# 18-OSPI_FLASH_AND_SPI_NOR_FLASH.net
KiCad netlist of a schematic drawn in Altium Designer
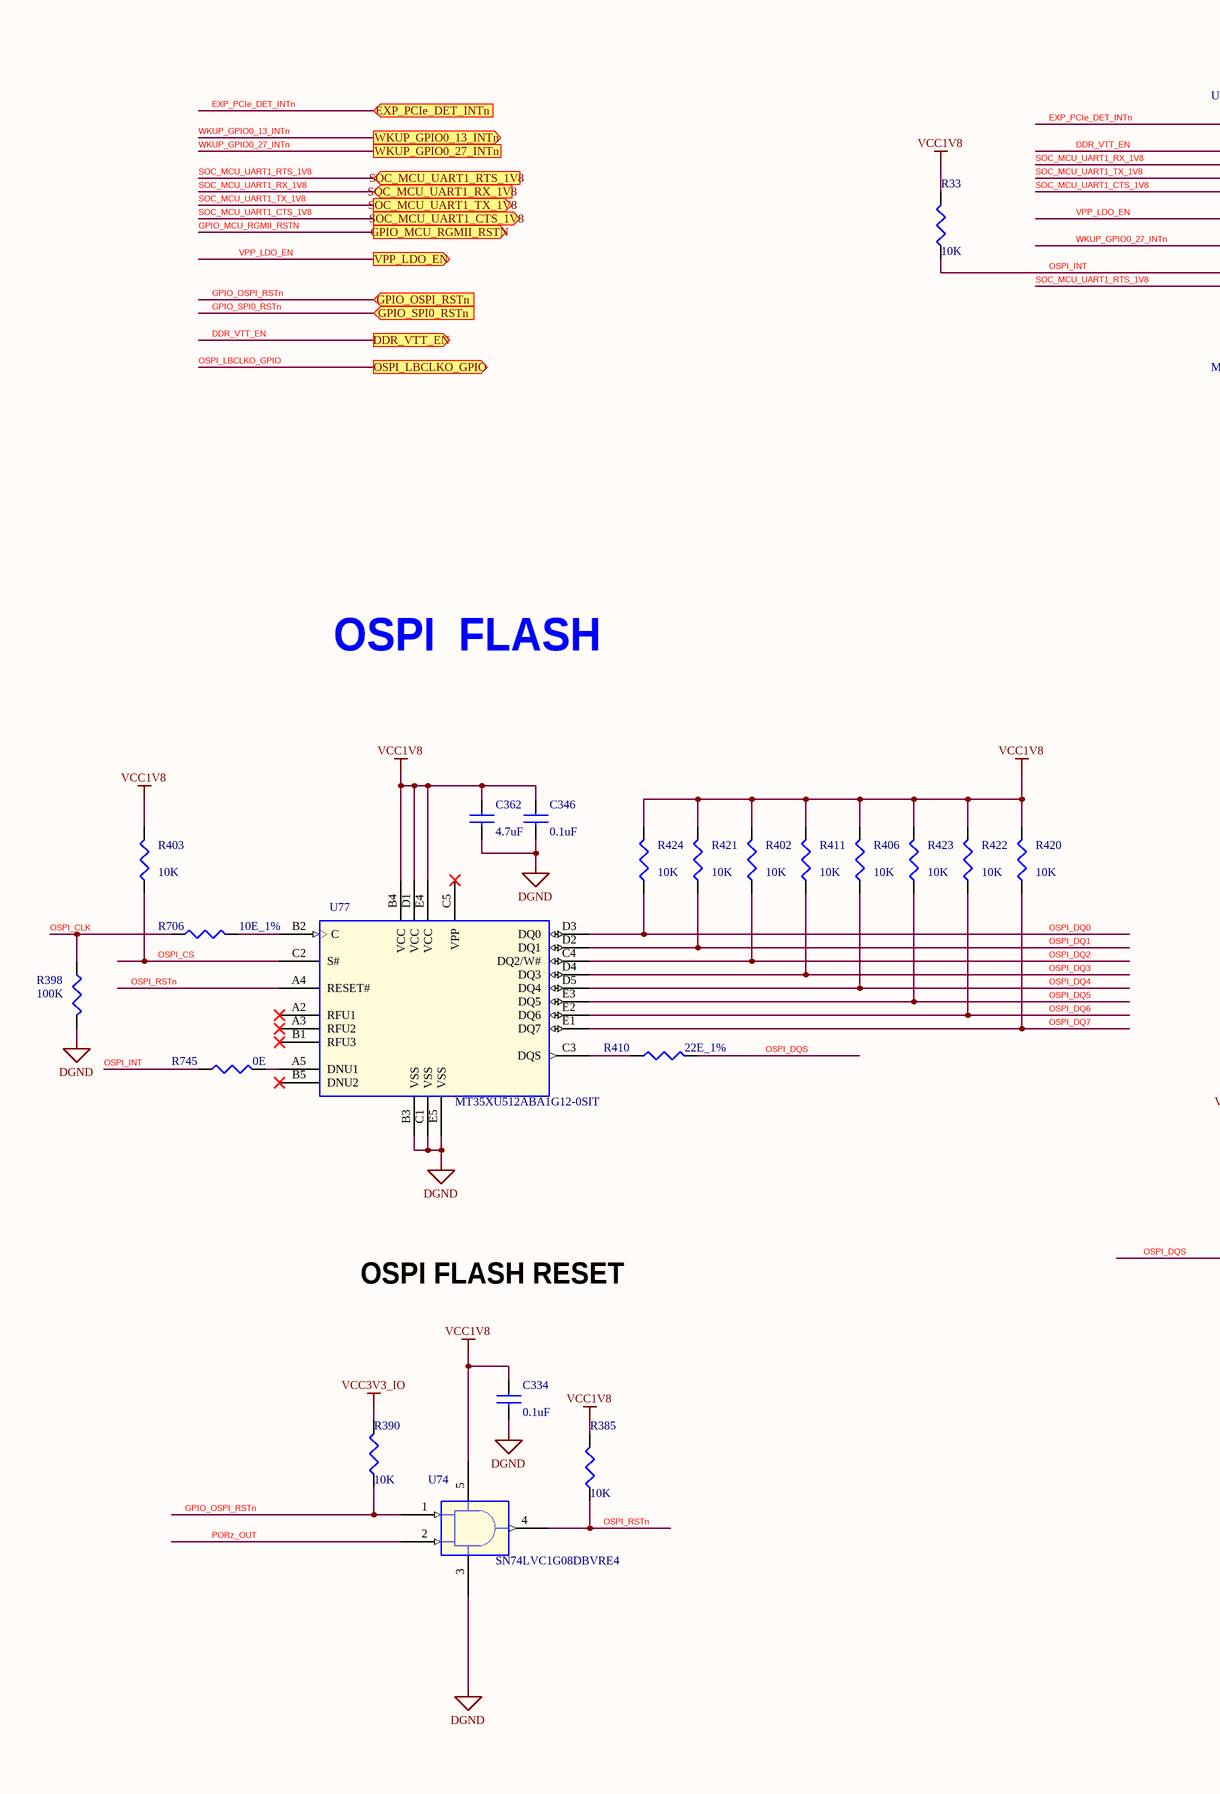
[diagram p0: 18-OSPI FLASH AND SPI NOR FLASH.SchDoc, left]
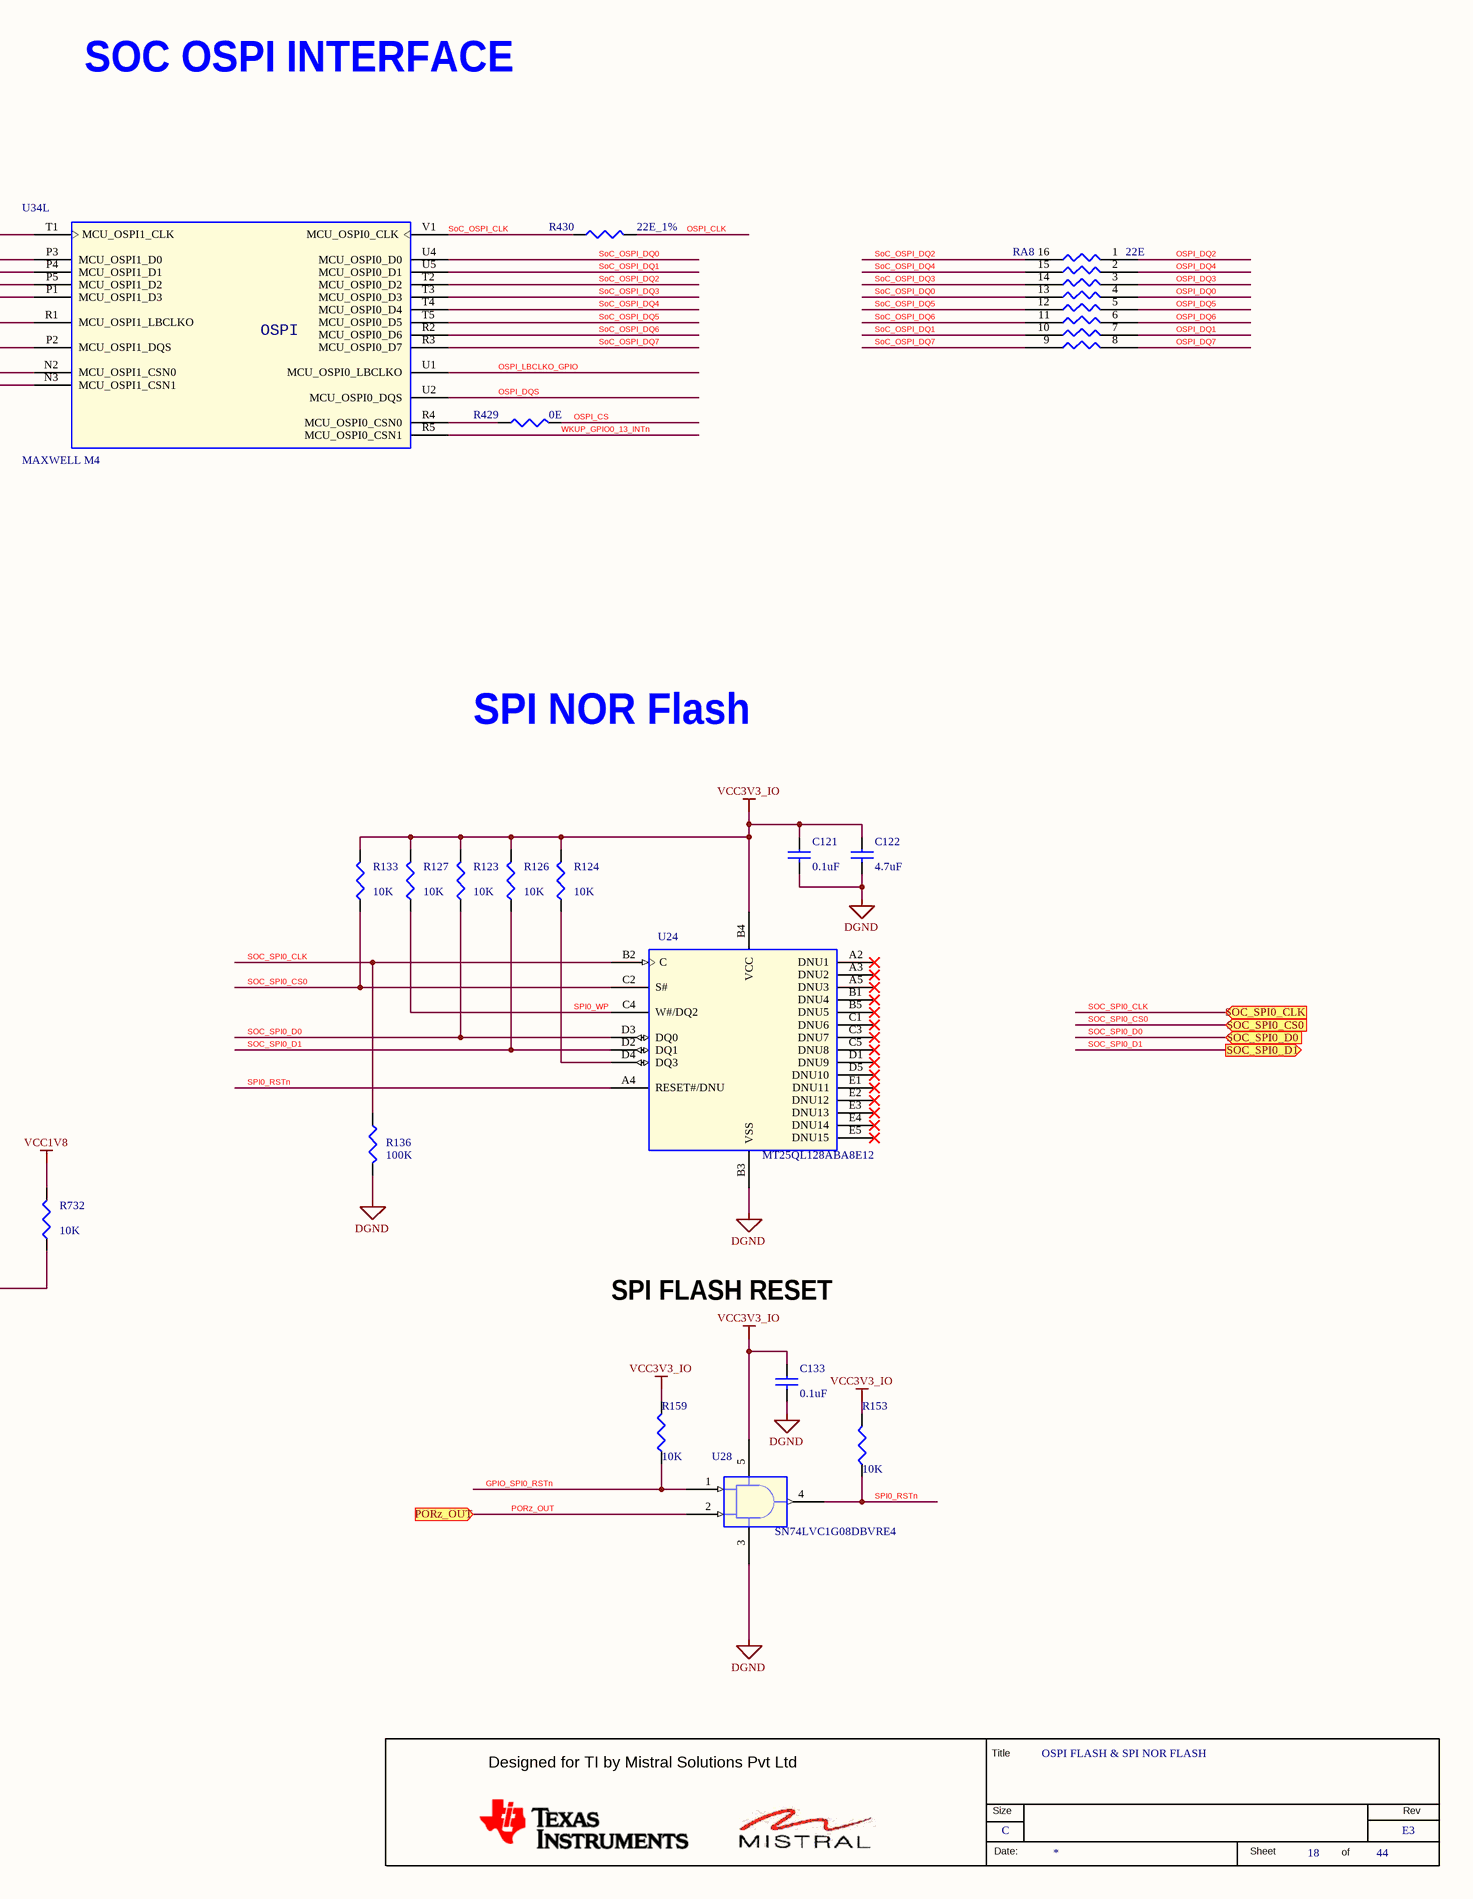
[diagram p1: 18-OSPI FLASH AND SPI NOR FLASH.SchDoc, right]

(export (version "E")
  (design (tool "Eeschema 10.0.6"))
  (components
    (comp (ref "C121")
      (value "0.1uF")
      (footprint "CAP0201_0-5")
      (description "CAP CERAMIC 0.1uF 16V 10% X5R 0201")
      (fields (field (name "DISTRIBUTOR_PART_NUMBER") "490-16742-1-ND") (field (name "VOLTAGE") "16V"))
      (libsource (lib "*") (part "CAP_Dup5"))
    )
    (comp (ref "C122")
      (value "4.7uF")
      (footprint "CAP0402_0-75")
      (description "CAP CERAMIC 4.7uF 10V 20% X5R 0402")
      (fields
        (field (name "MISTRAL PART NO") "120012060002-R")
        (field (name "MFR_PART_NUMBER") "0402ZD475MAT2A")
      )
      (libsource (lib "*") (part "CAP_Dup5"))
    )
    (comp (ref "C133")
      (value "0.1uF")
      (footprint "CAP0201_0-5")
      (description "CAP CERAMIC 0.1uF 16V 10% X5R 0201")
      (fields
        (field (name "MISTRAL PART NO") "120009030072-R")
        (field (name "MFR_PART_NUMBER") "GRM033R61C104KE84J")
      )
      (libsource (lib "*") (part "CAP_Dup5"))
    )
    (comp (ref "C334")
      (value "0.1uF")
      (footprint "CAP0201_0-5")
      (description "CAP CERAMIC 0.1uF 16V 10% X5R 0201")
      (fields (field (name "DISTRIBUTOR_PART_NUMBER") "490-16742-1-ND") (field (name "VOLTAGE") "16V"))
      (libsource (lib "*") (part "CAP_Dup5"))
    )
    (comp (ref "C346")
      (value "0.1uF")
      (footprint "CAP0201_0-5")
      (description "CAP CERAMIC 0.1uF 16V 10% X5R 0201")
      (fields (field (name "DISTRIBUTOR_PART_NUMBER") "490-16742-1-ND") (field (name "VOLTAGE") "16V"))
      (libsource (lib "*") (part "CAP_Dup5"))
    )
    (comp (ref "C362")
      (value "4.7uF")
      (footprint "CAP0402_0-75")
      (description "CAP CERAMIC 4.7uF 10V 20% X5R 0402")
      (fields (field (name "DISTRIBUTOR_PART_NUMBER") "478-10791-1-ND") (field (name "VOLTAGE") "10V"))
      (libsource (lib "*") (part "CAP_Dup5"))
    )
    (comp (ref "R33")
      (value "10K")
      (footprint "RES0402_0-5")
      (description "RES 10K 1/16W 5% 0402")
      (fields (field (name "DISTRIBUTOR_PART_NUMBER") "311-10KJRCT-ND") (field (name "VOLTAGE") "NA"))
      (libsource (lib "*") (part "RESISTOR_Dup5"))
    )
    (comp (ref "R123")
      (value "10K")
      (footprint "RES0402_0-5")
      (description "RES 10K 1/16W 5% 0402")
      (fields
        (field (name "MISTRAL PART NO") "110009030208-R")
        (field (name "MFR_PART_NUMBER") "RC0402JR-0710KL")
      )
      (libsource (lib "*") (part "RESISTOR_Dup5"))
    )
    (comp (ref "R124")
      (value "10K")
      (footprint "RES0402_0-5")
      (description "RES 10K 1/16W 5% 0402")
      (fields (field (name "DISTRIBUTOR_PART_NUMBER") "311-10KJRCT-ND") (field (name "VOLTAGE") "NA"))
      (libsource (lib "*") (part "RESISTOR_Dup5"))
    )
    (comp (ref "R126")
      (value "10K")
      (footprint "RES0402_0-5")
      (description "RES 10K 1/16W 5% 0402")
      (fields (field (name "DISTRIBUTOR_PART_NUMBER") "311-10KJRCT-ND") (field (name "VOLTAGE") "NA"))
      (libsource (lib "*") (part "RESISTOR_Dup5"))
    )
    (comp (ref "R127")
      (value "10K")
      (footprint "RES0402_0-5")
      (description "RES 10K 1/16W 5% 0402")
      (fields (field (name "DISTRIBUTOR_PART_NUMBER") "311-10KJRCT-ND") (field (name "VOLTAGE") "NA"))
      (libsource (lib "*") (part "RESISTOR_Dup5"))
    )
    (comp (ref "R133")
      (value "10K")
      (footprint "RES0402_0-5")
      (description "RES 10K 1/16W 5% 0402")
      (fields
        (field (name "MISTRAL PART NO") "110009030208-R")
        (field (name "MFR_PART_NUMBER") "RC0402JR-0710KL")
      )
      (libsource (lib "*") (part "RESISTOR_Dup5"))
    )
    (comp (ref "R136")
      (value "100K")
      (footprint "RES0402_0-5")
      (description "RES 100K 1/16W 5% 0402")
      (fields
        (field (name "MISTRAL PART NO") "110011060002-R")
        (field (name "MFR_PART_NUMBER") "CRCW0402100KJNED")
      )
      (libsource (lib "*") (part "RESISTOR_Dup4"))
    )
    (comp (ref "R153")
      (value "10K")
      (footprint "RES0402_0-5")
      (description "RES 10K 1/16W 5% 0402")
      (fields
        (field (name "MISTRAL PART NO") "110009030208-R")
        (field (name "MFR_PART_NUMBER") "RC0402JR-0710KL")
      )
      (libsource (lib "*") (part "RESISTOR_Dup5"))
    )
    (comp (ref "R159")
      (value "10K")
      (footprint "RES0402_0-5")
      (description "RES 10K 1/16W 5% 0402")
      (fields (field (name "DISTRIBUTOR_PART_NUMBER") "311-10KJRCT-ND") (field (name "VOLTAGE") "NA"))
      (libsource (lib "*") (part "RESISTOR_Dup5"))
    )
    (comp (ref "R385")
      (value "10K")
      (footprint "RES0402_0-5")
      (description "RES 10K 1/16W 5% 0402")
      (fields (field (name "DISTRIBUTOR_PART_NUMBER") "311-10KJRCT-ND") (field (name "VOLTAGE") "NA"))
      (libsource (lib "*") (part "RESISTOR_Dup5"))
    )
    (comp (ref "R390")
      (value "10K")
      (footprint "RES0402_0-5")
      (description "RES 10K 1/16W 5% 0402")
      (fields
        (field (name "MISTRAL PART NO") "110009030208-R")
        (field (name "MFR_PART_NUMBER") "RC0402JR-0710KL")
      )
      (libsource (lib "*") (part "RESISTOR_Dup5"))
    )
    (comp (ref "R398")
      (value "100K")
      (footprint "RES0402_0-5")
      (description "RES 100K 1/16W 5% 0402")
      (fields
        (field (name "MISTRAL PART NO") "110011060002-R")
        (field (name "MFR_PART_NUMBER") "CRCW0402100KJNED")
      )
      (libsource (lib "*") (part "RESISTOR_Dup4"))
    )
    (comp (ref "R402")
      (value "10K")
      (footprint "RES0402_0-5")
      (description "RES 10K 1/16W 5% 0402")
      (fields
        (field (name "MISTRAL PART NO") "110009030208-R")
        (field (name "MFR_PART_NUMBER") "RC0402JR-0710KL")
      )
      (libsource (lib "*") (part "RESISTOR_Dup5"))
    )
    (comp (ref "R403")
      (value "10K")
      (footprint "RES0402_0-5")
      (description "RES 10K 1/16W 5% 0402")
      (fields (field (name "DISTRIBUTOR_PART_NUMBER") "311-10KJRCT-ND") (field (name "VOLTAGE") "NA"))
      (libsource (lib "*") (part "RESISTOR_Dup5"))
    )
    (comp (ref "R406")
      (value "10K")
      (footprint "RES0402_0-5")
      (description "RES 10K 1/16W 5% 0402")
      (fields
        (field (name "MISTRAL PART NO") "110009030208-R")
        (field (name "MFR_PART_NUMBER") "RC0402JR-0710KL")
      )
      (libsource (lib "*") (part "RESISTOR_Dup5"))
    )
    (comp (ref "R410")
      (value "22E_1%")
      (footprint "RES0402")
      (description "RES 22E 1/16W 1% 0402")
      (fields
        (field (name "MISTRAL PART NO") "110009090004-P")
        (field (name "MFR_PART_NUMBER") "RC0402FR-0722RL")
      )
      (libsource (lib "*") (part "RESISTOR_Dup4"))
    )
    (comp (ref "R411")
      (value "10K")
      (footprint "RES0402_0-5")
      (description "RES 10K 1/16W 5% 0402")
      (fields (field (name "DISTRIBUTOR_PART_NUMBER") "311-10KJRCT-ND") (field (name "VOLTAGE") "NA"))
      (libsource (lib "*") (part "RESISTOR_Dup5"))
    )
    (comp (ref "R420")
      (value "10K")
      (footprint "RES0402_0-5")
      (description "RES 10K 1/16W 5% 0402")
      (fields
        (field (name "MISTRAL PART NO") "110009030208-R")
        (field (name "MFR_PART_NUMBER") "RC0402JR-0710KL")
      )
      (libsource (lib "*") (part "RESISTOR_Dup5"))
    )
    (comp (ref "R421")
      (value "10K")
      (footprint "RES0402_0-5")
      (description "RES 10K 1/16W 5% 0402")
      (fields (field (name "DISTRIBUTOR_PART_NUMBER") "311-10KJRCT-ND") (field (name "VOLTAGE") "NA"))
      (libsource (lib "*") (part "RESISTOR_Dup5"))
    )
    (comp (ref "R422")
      (value "10K")
      (footprint "RES0402_0-5")
      (description "RES 10K 1/16W 5% 0402")
      (fields (field (name "DISTRIBUTOR_PART_NUMBER") "311-10KJRCT-ND") (field (name "VOLTAGE") "NA"))
      (libsource (lib "*") (part "RESISTOR_Dup5"))
    )
    (comp (ref "R423")
      (value "10K")
      (footprint "RES0402_0-5")
      (description "RES 10K 1/16W 5% 0402")
      (fields
        (field (name "MISTRAL PART NO") "110009030208-R")
        (field (name "MFR_PART_NUMBER") "RC0402JR-0710KL")
      )
      (libsource (lib "*") (part "RESISTOR_Dup5"))
    )
    (comp (ref "R424")
      (value "10K")
      (footprint "RES0402_0-5")
      (description "RES 10K 1/16W 5% 0402")
      (fields (field (name "DISTRIBUTOR_PART_NUMBER") "311-10KJRCT-ND") (field (name "VOLTAGE") "NA"))
      (libsource (lib "*") (part "RESISTOR_Dup5"))
    )
    (comp (ref "R429")
      (value "0E")
      (footprint "RES0402_0-5")
      (description "RES 0E 1/16W 0402")
      (fields
        (field (name "MISTRAL PART NO") "110010080019-P")
        (field (name "MFR_PART_NUMBER") "CRCW04020000Z0ED")
      )
      (libsource (lib "*") (part "RESISTOR_Dup4"))
    )
    (comp (ref "R430")
      (value "22E_1%")
      (footprint "RES0402")
      (description "RES 22E 1/16W 1% 0402")
      (fields
        (field (name "CUST_PART_NUMBER") "4700-80047E")
        (field (name "DISTRIBUTOR_PART_NUMBER") "311-22.0LRCT-ND")
      )
      (libsource (lib "*") (part "RESISTOR_Dup4"))
    )
    (comp (ref "R706")
      (value "10E_1%")
      (footprint "TMDX654GPEVM_BRD:RES0402_0-5")
      (description "RES 10E 1/16W 1% 0402")
      (fields (field (name "DISTRIBUTOR_PART_NUMBER") "311-10.0LRCT-ND") (field (name "TOLERANCE") "1%"))
      (libsource (lib "*") (part "RESISTOR_Dup2"))
    )
    (comp (ref "R732")
      (value "10K")
      (footprint "RES0402_0-5")
      (description "RES 10K 1/16W 5% 0402")
      (fields (field (name "DISTRIBUTOR_PART_NUMBER") "311-10KJRCT-ND") (field (name "VOLTAGE") "NA"))
      (libsource (lib "*") (part "RESISTOR_Dup5"))
    )
    (comp (ref "R745")
      (value "0E")
      (footprint "RES0402_0-5")
      (description "RES 0E 1/16W 0402")
      (fields
        (field (name "MISTRAL PART NO") "110010080019-P")
        (field (name "MFR_PART_NUMBER") "CRCW04020000Z0ED")
      )
      (libsource (lib "*") (part "RESISTOR_Dup4"))
    )
    (comp (ref "RA8")
      (value "22E")
      (footprint "RESA_0402-8")
      (description "RES ARRAY 22E 62.5mW 5% 0402")
      (fields (field (name "DISTRIBUTOR_PART_NUMBER") "741X163220JPCT-ND") (field (name "TOLERANCE") "5%"))
      (libsource (lib "*") (part "RESARR_ISO8"))
    )
    (comp (ref "U24")
      (value "MT25QL128ABA8E12")
      (footprint "TPBGA24_39-37_240X320_1-2")
      (description "IC 128Mb SERIAL NOR FLASH MEMORY TPBGA24")
      (fields
        (field (name "MISTRAL PART NO") "141117090006-R")
        (field (name "MFR_PART_NUMBER") "MT25QL128ABA8E12-0SIT")
      )
      (libsource (lib "*") (part "MT25QL02GCBB8E12_TPBGA24"))
    )
    (comp (ref "U28")
      (value "SN74LVC1G08DBVRE4")
      (footprint "SOT23-5")
      (description "IC SINGLE 2-INPUT POSITIVE AND GATE SOT23-5")
      (fields
        (field (name "DISTRIBUTOR_PART_NUMBER") "SN74LVC1G08DBVRE4-ND")
        (field (name "MISTRAL PART NO") "141009060026-R")
      )
      (libsource (lib "*") (part "SN74LVC1G08DBVRE4_SOT23-5"))
    )
    (comp (ref "U34")
      (value "MAXWELL M4")
      (footprint "BGA784_31-49_910X910_1-7")
      (description "IC MAXWELL MICRO CONTROLLER UNIT BGA784")
      (fields
        (field (name "MISTRAL PART NO") "141217100003")
        (field (name "MFR_PART_NUMBER") "MAXWELL M4_EVM")
      )
      (libsource (lib "*") (part "AM654X_BGA784"))
    )
    (comp (ref "U74")
      (value "SN74LVC1G08DBVRE4")
      (footprint "SOT23-5")
      (description "IC SINGLE 2-INPUT POSITIVE AND GATE SOT23-5")
      (fields
        (field (name "MISTRAL PART NO") "141009060026-R")
        (field (name "DISTRIBUTOR_PART_NUMBER") "SN74LVC1G08DBVRE4-ND")
      )
      (libsource (lib "*") (part "SN74LVC1G08DBVRE4_SOT23-5"))
    )
    (comp (ref "U77")
      (value "MT35XU512ABA1G12-0SIT")
      (footprint "TPBGA24_39-37_240X320_1-2")
      (description "IC 512Mb XCCELA FLASH MEMORY TPBGA24")
      (fields (field (name "DISTRIBUTOR_PART_NUMBER") "NA") (field (name "MISTRAL PART NO") "141117080009-R"))
      (libsource (lib "*") (part "MT35XU512ABA1G12_TPBGA24"))
    )
  )
  (nets
    (net (code "1") (name "/DDR_VTT_EN") (class "Default")
      (node (ref "U34") (pin "P3") (pinfunction "MCU_OSPI1_D0_P3") (pintype "passive"))
    )
    (net (code "2") (name "/EXP_PCIe_DET_INTn") (class "Default")
      (node (ref "U34") (pin "T1") (pinfunction "MCU_OSPI1_CLK_T1") (pintype "passive"))
    )
    (net (code "4") (name "/GPIO_OSPI_RSTn") (class "Default")
      (node (ref "R390") (pin "1") (pinfunction "1_1") (pintype "passive"))
      (node (ref "U74") (pin "1") (pinfunction "A_1") (pintype "input"))
    )
    (net (code "5") (name "/GPIO_SPI0_RSTn") (class "Default")
      (node (ref "R159") (pin "1") (pinfunction "1_1") (pintype "passive"))
      (node (ref "U28") (pin "1") (pinfunction "A_1") (pintype "input"))
    )
    (net (code "6") (name "/OSPI_CLK") (class "Default")
      (node (ref "R398") (pin "1") (pinfunction "1_1") (pintype "passive"))
      (node (ref "R430") (pin "2") (pinfunction "2_2") (pintype "passive"))
      (node (ref "R706") (pin "1") (pinfunction "1_1") (pintype "passive"))
    )
    (net (code "7") (name "/OSPI_CS") (class "Default")
      (node (ref "R403") (pin "1") (pinfunction "1_1") (pintype "passive"))
      (node (ref "R429") (pin "2") (pinfunction "2_2") (pintype "passive"))
      (node (ref "U77") (pin "C2") (pinfunction "S#_C2") (pintype "passive"))
    )
    (net (code "8") (name "/OSPI_DQ0") (class "Default")
      (node (ref "R424") (pin "1") (pinfunction "1_1") (pintype "passive"))
      (node (ref "RA8") (pin "4") (pinfunction "4_4") (pintype "passive"))
      (node (ref "U77") (pin "D3") (pinfunction "DQ0_D3") (pintype "bidirectional"))
    )
    (net (code "9") (name "/OSPI_DQ1") (class "Default")
      (node (ref "R421") (pin "1") (pinfunction "1_1") (pintype "passive"))
      (node (ref "RA8") (pin "7") (pinfunction "7_7") (pintype "passive"))
      (node (ref "U77") (pin "D2") (pinfunction "DQ1_D2") (pintype "bidirectional"))
    )
    (net (code "10") (name "/OSPI_DQ2") (class "Default")
      (node (ref "R402") (pin "1") (pinfunction "1_1") (pintype "passive"))
      (node (ref "RA8") (pin "1") (pinfunction "1_1") (pintype "passive"))
      (node (ref "U77") (pin "C4") (pinfunction "DQ2/W#_C4") (pintype "bidirectional"))
    )
    (net (code "11") (name "/OSPI_DQ3") (class "Default")
      (node (ref "R411") (pin "1") (pinfunction "1_1") (pintype "passive"))
      (node (ref "RA8") (pin "3") (pinfunction "3_3") (pintype "passive"))
      (node (ref "U77") (pin "D4") (pinfunction "DQ3_D4") (pintype "bidirectional"))
    )
    (net (code "12") (name "/OSPI_DQ4") (class "Default")
      (node (ref "R406") (pin "1") (pinfunction "1_1") (pintype "passive"))
      (node (ref "RA8") (pin "2") (pinfunction "2_2") (pintype "passive"))
      (node (ref "U77") (pin "D5") (pinfunction "DQ4_D5") (pintype "bidirectional"))
    )
    (net (code "13") (name "/OSPI_DQ5") (class "Default")
      (node (ref "R423") (pin "1") (pinfunction "1_1") (pintype "passive"))
      (node (ref "RA8") (pin "5") (pinfunction "5_5") (pintype "passive"))
      (node (ref "U77") (pin "E3") (pinfunction "DQ5_E3") (pintype "bidirectional"))
    )
    (net (code "14") (name "/OSPI_DQ6") (class "Default")
      (node (ref "R422") (pin "1") (pinfunction "1_1") (pintype "passive"))
      (node (ref "RA8") (pin "6") (pinfunction "6_6") (pintype "passive"))
      (node (ref "U77") (pin "E2") (pinfunction "DQ6_E2") (pintype "bidirectional"))
    )
    (net (code "15") (name "/OSPI_DQ7") (class "Default")
      (node (ref "R420") (pin "1") (pinfunction "1_1") (pintype "passive"))
      (node (ref "RA8") (pin "8") (pinfunction "8_8") (pintype "passive"))
      (node (ref "U77") (pin "E1") (pinfunction "DQ7_E1") (pintype "bidirectional"))
    )
    (net (code "16") (name "/OSPI_DQS") (class "Default")
      (node (ref "R410") (pin "2") (pinfunction "2_2") (pintype "passive"))
      (node (ref "R732") (pin "1") (pinfunction "1_1") (pintype "passive"))
      (node (ref "U34") (pin "U2") (pinfunction "MCU_OSPI0_DQS_U2") (pintype "passive"))
    )
    (net (code "17") (name "/OSPI_INT") (class "Default")
      (node (ref "R33") (pin "1") (pinfunction "1_1") (pintype "passive"))
      (node (ref "R745") (pin "1") (pinfunction "1_1") (pintype "passive"))
      (node (ref "U34") (pin "N2") (pinfunction "MCU_OSPI1_CSN0_N2") (pintype "passive"))
    )
    (net (code "18") (name "/OSPI_LBCLKO_GPIO") (class "Default")
      (node (ref "U34") (pin "U1") (pinfunction "MCU_OSPI0_LBCLKO_U1") (pintype "passive"))
    )
    (net (code "19") (name "/OSPI_RSTn") (class "Default")
      (node (ref "R385") (pin "1") (pinfunction "1_1") (pintype "passive"))
      (node (ref "U74") (pin "4") (pinfunction "Y_4") (pintype "output"))
      (node (ref "U77") (pin "A4") (pinfunction "RESET#_A4") (pintype "passive"))
    )
    (net (code "20") (name "/PORz_OUT") (class "Default")
      (node (ref "U28") (pin "2") (pinfunction "B_2") (pintype "input"))
      (node (ref "U74") (pin "2") (pinfunction "B_2") (pintype "input"))
    )
    (net (code "21") (name "/SOC_MCU_UART1_CTS_1V8") (class "Default")
      (node (ref "U34") (pin "P1") (pinfunction "MCU_OSPI1_D3_P1") (pintype "passive"))
    )
    (net (code "22") (name "/SOC_MCU_UART1_RTS_1V8") (class "Default")
      (node (ref "U34") (pin "N3") (pinfunction "MCU_OSPI1_CSN1_N3") (pintype "passive"))
    )
    (net (code "23") (name "/SOC_MCU_UART1_RX_1V8") (class "Default")
      (node (ref "U34") (pin "P4") (pinfunction "MCU_OSPI1_D1_P4") (pintype "passive"))
    )
    (net (code "24") (name "/SOC_MCU_UART1_TX_1V8") (class "Default")
      (node (ref "U34") (pin "P5") (pinfunction "MCU_OSPI1_D2_P5") (pintype "passive"))
    )
    (net (code "25") (name "/SOC_SPI0_CLK") (class "Default")
      (node (ref "R136") (pin "1") (pinfunction "1_1") (pintype "passive"))
      (node (ref "U24") (pin "B2") (pinfunction "C_B2") (pintype "input"))
    )
    (net (code "26") (name "/SOC_SPI0_CS0") (class "Default")
      (node (ref "R133") (pin "1") (pinfunction "1_1") (pintype "passive"))
      (node (ref "U24") (pin "C2") (pinfunction "S#_C2") (pintype "passive"))
    )
    (net (code "27") (name "/SOC_SPI0_D0") (class "Default")
      (node (ref "R123") (pin "1") (pinfunction "1_1") (pintype "passive"))
      (node (ref "U24") (pin "D3") (pinfunction "DQ0_D3") (pintype "bidirectional"))
    )
    (net (code "28") (name "/SOC_SPI0_D1") (class "Default")
      (node (ref "R126") (pin "1") (pinfunction "1_1") (pintype "passive"))
      (node (ref "U24") (pin "D2") (pinfunction "DQ1_D2") (pintype "bidirectional"))
    )
    (net (code "29") (name "/SPI0_RSTn") (class "Default")
      (node (ref "R153") (pin "1") (pinfunction "1_1") (pintype "passive"))
      (node (ref "U24") (pin "A4") (pinfunction "RESET#/DNU_A4") (pintype "passive"))
      (node (ref "U28") (pin "4") (pinfunction "Y_4") (pintype "output"))
    )
    (net (code "30") (name "/SPI0_WP") (class "Default")
      (node (ref "R127") (pin "1") (pinfunction "1_1") (pintype "passive"))
      (node (ref "U24") (pin "C4") (pinfunction "W#/DQ2_C4") (pintype "passive"))
    )
    (net (code "31") (name "/SoC_OSPI_CLK") (class "Default")
      (node (ref "R430") (pin "1") (pinfunction "1_1") (pintype "passive"))
      (node (ref "U34") (pin "V1") (pinfunction "MCU_OSPI0_CLK_V1") (pintype "passive"))
    )
    (net (code "32") (name "/SoC_OSPI_DQ0") (class "Default")
      (node (ref "RA8") (pin "13") (pinfunction "13_13") (pintype "passive"))
      (node (ref "U34") (pin "U4") (pinfunction "MCU_OSPI0_D0_U4") (pintype "passive"))
    )
    (net (code "33") (name "/SoC_OSPI_DQ1") (class "Default")
      (node (ref "RA8") (pin "10") (pinfunction "10_10") (pintype "passive"))
      (node (ref "U34") (pin "U5") (pinfunction "MCU_OSPI0_D1_U5") (pintype "passive"))
    )
    (net (code "34") (name "/SoC_OSPI_DQ2") (class "Default")
      (node (ref "RA8") (pin "16") (pinfunction "16_16") (pintype "passive"))
      (node (ref "U34") (pin "T2") (pinfunction "MCU_OSPI0_D2_T2") (pintype "passive"))
    )
    (net (code "35") (name "/SoC_OSPI_DQ3") (class "Default")
      (node (ref "RA8") (pin "14") (pinfunction "14_14") (pintype "passive"))
      (node (ref "U34") (pin "T3") (pinfunction "MCU_OSPI0_D3_T3") (pintype "passive"))
    )
    (net (code "36") (name "/SoC_OSPI_DQ4") (class "Default")
      (node (ref "RA8") (pin "15") (pinfunction "15_15") (pintype "passive"))
      (node (ref "U34") (pin "T4") (pinfunction "MCU_OSPI0_D4_T4") (pintype "passive"))
    )
    (net (code "37") (name "/SoC_OSPI_DQ5") (class "Default")
      (node (ref "RA8") (pin "12") (pinfunction "12_12") (pintype "passive"))
      (node (ref "U34") (pin "T5") (pinfunction "MCU_OSPI0_D5_T5") (pintype "passive"))
    )
    (net (code "38") (name "/SoC_OSPI_DQ6") (class "Default")
      (node (ref "RA8") (pin "11") (pinfunction "11_11") (pintype "passive"))
      (node (ref "U34") (pin "R2") (pinfunction "MCU_OSPI0_D6_R2") (pintype "passive"))
    )
    (net (code "39") (name "/SoC_OSPI_DQ7") (class "Default")
      (node (ref "RA8") (pin "9") (pinfunction "9_9") (pintype "passive"))
      (node (ref "U34") (pin "R3") (pinfunction "MCU_OSPI0_D7_R3") (pintype "passive"))
    )
    (net (code "40") (name "/VPP_LDO_EN") (class "Default")
      (node (ref "U34") (pin "R1") (pinfunction "MCU_OSPI1_LBCLKO_R1") (pintype "passive"))
    )
    (net (code "41") (name "/WKUP_GPIO0_13_INTn") (class "Default")
      (node (ref "U34") (pin "R5") (pinfunction "MCU_OSPI0_CSN1_R5") (pintype "passive"))
    )
    (net (code "42") (name "/WKUP_GPIO0_27_INTn") (class "Default")
      (node (ref "U34") (pin "P2") (pinfunction "MCU_OSPI1_DQS_P2") (pintype "passive"))
    )
    (net (code "43") (name "DGND") (class "Default")
      (node (ref "C121") (pin "2") (pinfunction "2_2") (pintype "passive"))
      (node (ref "C122") (pin "2") (pinfunction "2_2") (pintype "passive"))
      (node (ref "C133") (pin "2") (pinfunction "2_2") (pintype "passive"))
      (node (ref "C334") (pin "2") (pinfunction "2_2") (pintype "passive"))
      (node (ref "C346") (pin "2") (pinfunction "2_2") (pintype "passive"))
      (node (ref "C362") (pin "2") (pinfunction "2_2") (pintype "passive"))
      (node (ref "R136") (pin "2") (pinfunction "2_2") (pintype "passive"))
      (node (ref "R398") (pin "2") (pinfunction "2_2") (pintype "passive"))
      (node (ref "U24") (pin "B3") (pinfunction "VSS_B3") (pintype "power_in"))
      (node (ref "U28") (pin "3") (pinfunction "GND_3") (pintype "power_in"))
      (node (ref "U74") (pin "3") (pinfunction "GND_3") (pintype "power_in"))
      (node (ref "U77") (pin "B3") (pinfunction "VSS_B3") (pintype "power_in"))
      (node (ref "U77") (pin "C1") (pinfunction "VSS_C1") (pintype "power_in"))
      (node (ref "U77") (pin "E5") (pinfunction "VSS_E5") (pintype "power_in"))
    )
    (net (code "44") (name "Net-(U24-DQ3)") (class "Default")
      (node (ref "R124") (pin "1") (pinfunction "1_1") (pintype "passive"))
      (node (ref "U24") (pin "D4") (pinfunction "DQ3_D4") (pintype "bidirectional"))
    )
    (net (code "45") (name "Net-(U34L-MCU_OSPI0_CSN0)") (class "Default")
      (node (ref "R429") (pin "1") (pinfunction "1_1") (pintype "passive"))
      (node (ref "U34") (pin "R4") (pinfunction "MCU_OSPI0_CSN0_R4") (pintype "passive"))
    )
    (net (code "46") (name "Net-(U77-C)") (class "Default")
      (node (ref "R706") (pin "2") (pinfunction "2_2") (pintype "passive"))
      (node (ref "U77") (pin "B2") (pinfunction "C_B2") (pintype "input"))
    )
    (net (code "47") (name "Net-(U77-DNU1)") (class "Default")
      (node (ref "R745") (pin "2") (pinfunction "2_2") (pintype "passive"))
      (node (ref "U77") (pin "A5") (pinfunction "DNU1_A5") (pintype "passive"))
    )
    (net (code "48") (name "Net-(U77-DQS)") (class "Default")
      (node (ref "R410") (pin "1") (pinfunction "1_1") (pintype "passive"))
      (node (ref "U77") (pin "C3") (pinfunction "DQS_C3") (pintype "output"))
    )
    (net (code "49") (name "VCC1V8") (class "Default")
      (node (ref "C334") (pin "1") (pinfunction "1_1") (pintype "passive"))
      (node (ref "C346") (pin "1") (pinfunction "1_1") (pintype "passive"))
      (node (ref "C362") (pin "1") (pinfunction "1_1") (pintype "passive"))
      (node (ref "R33") (pin "2") (pinfunction "2_2") (pintype "passive"))
      (node (ref "R385") (pin "2") (pinfunction "2_2") (pintype "passive"))
      (node (ref "R402") (pin "2") (pinfunction "2_2") (pintype "passive"))
      (node (ref "R403") (pin "2") (pinfunction "2_2") (pintype "passive"))
      (node (ref "R406") (pin "2") (pinfunction "2_2") (pintype "passive"))
      (node (ref "R411") (pin "2") (pinfunction "2_2") (pintype "passive"))
      (node (ref "R420") (pin "2") (pinfunction "2_2") (pintype "passive"))
      (node (ref "R421") (pin "2") (pinfunction "2_2") (pintype "passive"))
      (node (ref "R422") (pin "2") (pinfunction "2_2") (pintype "passive"))
      (node (ref "R423") (pin "2") (pinfunction "2_2") (pintype "passive"))
      (node (ref "R424") (pin "2") (pinfunction "2_2") (pintype "passive"))
      (node (ref "R732") (pin "2") (pinfunction "2_2") (pintype "passive"))
      (node (ref "U74") (pin "5") (pinfunction "VCC_5") (pintype "power_in"))
      (node (ref "U77") (pin "B4") (pinfunction "VCC_B4") (pintype "power_in"))
      (node (ref "U77") (pin "D1") (pinfunction "VCC_D1") (pintype "power_in"))
      (node (ref "U77") (pin "E4") (pinfunction "VCC_E4") (pintype "power_in"))
    )
    (net (code "50") (name "VCC3V3_IO") (class "Default")
      (node (ref "C121") (pin "1") (pinfunction "1_1") (pintype "passive"))
      (node (ref "C122") (pin "1") (pinfunction "1_1") (pintype "passive"))
      (node (ref "C133") (pin "1") (pinfunction "1_1") (pintype "passive"))
      (node (ref "R123") (pin "2") (pinfunction "2_2") (pintype "passive"))
      (node (ref "R124") (pin "2") (pinfunction "2_2") (pintype "passive"))
      (node (ref "R126") (pin "2") (pinfunction "2_2") (pintype "passive"))
      (node (ref "R127") (pin "2") (pinfunction "2_2") (pintype "passive"))
      (node (ref "R133") (pin "2") (pinfunction "2_2") (pintype "passive"))
      (node (ref "R153") (pin "2") (pinfunction "2_2") (pintype "passive"))
      (node (ref "R159") (pin "2") (pinfunction "2_2") (pintype "passive"))
      (node (ref "R390") (pin "2") (pinfunction "2_2") (pintype "passive"))
      (node (ref "U24") (pin "B4") (pinfunction "VCC_B4") (pintype "power_in"))
      (node (ref "U28") (pin "5") (pinfunction "VCC_5") (pintype "power_in"))
    )
    (net (code "51") (name "unconnected-(U24-DNU1-PadA2)") (class "Default")
      (node (ref "U24") (pin "A2") (pinfunction "DNU1_A2") (pintype "passive+no_connect"))
    )
    (net (code "52") (name "unconnected-(U24-DNU2-PadA3)") (class "Default")
      (node (ref "U24") (pin "A3") (pinfunction "DNU2_A3") (pintype "passive+no_connect"))
    )
    (net (code "53") (name "unconnected-(U24-DNU3-PadA5)") (class "Default")
      (node (ref "U24") (pin "A5") (pinfunction "DNU3_A5") (pintype "passive+no_connect"))
    )
    (net (code "54") (name "unconnected-(U24-DNU4-PadB1)") (class "Default")
      (node (ref "U24") (pin "B1") (pinfunction "DNU4_B1") (pintype "passive+no_connect"))
    )
    (net (code "55") (name "unconnected-(U24-DNU5-PadB5)") (class "Default")
      (node (ref "U24") (pin "B5") (pinfunction "DNU5_B5") (pintype "passive+no_connect"))
    )
    (net (code "56") (name "unconnected-(U24-DNU6-PadC1)") (class "Default")
      (node (ref "U24") (pin "C1") (pinfunction "DNU6_C1") (pintype "passive+no_connect"))
    )
    (net (code "57") (name "unconnected-(U24-DNU7-PadC3)") (class "Default")
      (node (ref "U24") (pin "C3") (pinfunction "DNU7_C3") (pintype "passive+no_connect"))
    )
    (net (code "58") (name "unconnected-(U24-DNU8-PadC5)") (class "Default")
      (node (ref "U24") (pin "C5") (pinfunction "DNU8_C5") (pintype "passive+no_connect"))
    )
    (net (code "59") (name "unconnected-(U24-DNU9-PadD1)") (class "Default")
      (node (ref "U24") (pin "D1") (pinfunction "DNU9_D1") (pintype "passive+no_connect"))
    )
    (net (code "60") (name "unconnected-(U24-DNU10-PadD5)") (class "Default")
      (node (ref "U24") (pin "D5") (pinfunction "DNU10_D5") (pintype "passive+no_connect"))
    )
    (net (code "61") (name "unconnected-(U24-DNU11-PadE1)") (class "Default")
      (node (ref "U24") (pin "E1") (pinfunction "DNU11_E1") (pintype "passive+no_connect"))
    )
    (net (code "62") (name "unconnected-(U24-DNU12-PadE2)") (class "Default")
      (node (ref "U24") (pin "E2") (pinfunction "DNU12_E2") (pintype "passive+no_connect"))
    )
    (net (code "63") (name "unconnected-(U24-DNU13-PadE3)") (class "Default")
      (node (ref "U24") (pin "E3") (pinfunction "DNU13_E3") (pintype "passive+no_connect"))
    )
    (net (code "64") (name "unconnected-(U24-DNU14-PadE4)") (class "Default")
      (node (ref "U24") (pin "E4") (pinfunction "DNU14_E4") (pintype "passive+no_connect"))
    )
    (net (code "65") (name "unconnected-(U24-DNU15-PadE5)") (class "Default")
      (node (ref "U24") (pin "E5") (pinfunction "DNU15_E5") (pintype "passive+no_connect"))
    )
    (net (code "66") (name "unconnected-(U77-DNU2-PadB5)") (class "Default")
      (node (ref "U77") (pin "B5") (pinfunction "DNU2_B5") (pintype "passive+no_connect"))
    )
    (net (code "67") (name "unconnected-(U77-RFU1-PadA2)") (class "Default")
      (node (ref "U77") (pin "A2") (pinfunction "RFU1_A2") (pintype "passive+no_connect"))
    )
    (net (code "68") (name "unconnected-(U77-RFU2-PadA3)") (class "Default")
      (node (ref "U77") (pin "A3") (pinfunction "RFU2_A3") (pintype "passive+no_connect"))
    )
    (net (code "69") (name "unconnected-(U77-RFU3-PadB1)") (class "Default")
      (node (ref "U77") (pin "B1") (pinfunction "RFU3_B1") (pintype "passive+no_connect"))
    )
    (net (code "70") (name "unconnected-(U77-VPP-PadC5)") (class "Default")
      (node (ref "U77") (pin "C5") (pinfunction "VPP_C5") (pintype "power_in+no_connect"))
    )
  )
)
